# Strobe.net
KiCad netlist of a schematic drawn in EAGLE
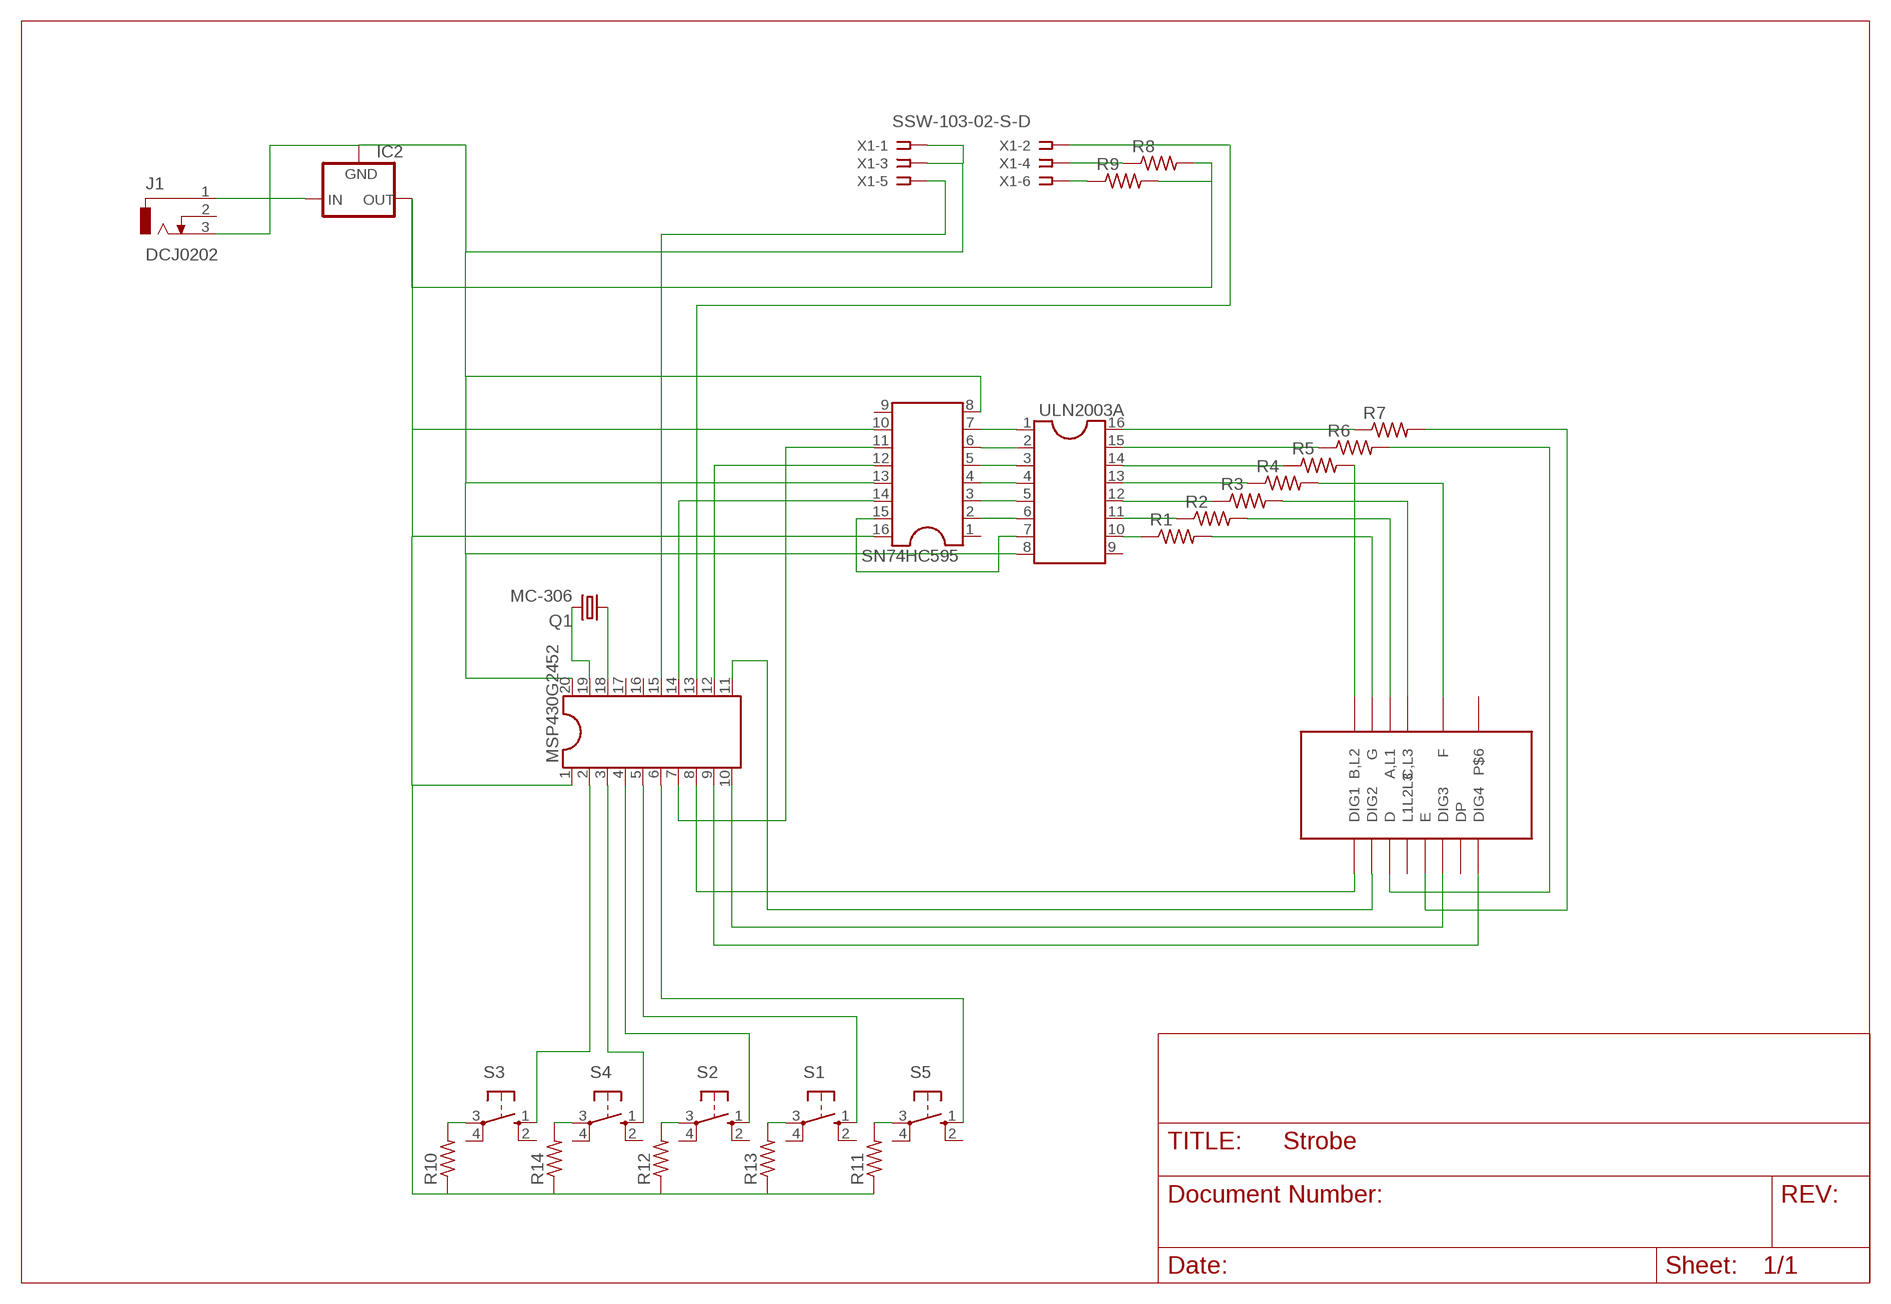
[diagram p0: schematic, sheet 1]

(export (version "E")
  (design (tool "Eeschema 10.0.6"))
  (components
    (comp (ref "IC2")
      (value "78XXS")
      (footprint "eagle-import:78XXS")
      (libsource (lib "eagle-import") (part "78XXS"))
    )
    (comp (ref "J1")
      (value "DCJ0202")
      (footprint "eagle-import:DCJ0202")
      (libsource (lib "eagle-import") (part "DCJ0202"))
    )
    (comp (ref "LTC-4627JS")
      (value "SEG4X7")
      (footprint "eagle-import:HDSP-R")
      (libsource (lib "eagle-import") (part "SEG4X7"))
    )
    (comp (ref "MSP430G2452")
      (value "DIL20S")
      (footprint "eagle-import:SOCKET-20")
      (libsource (lib "eagle-import") (part "DIL20S"))
    )
    (comp (ref "Q1")
      (value "MC-306")
      (footprint "eagle-import:MC-306")
      (fields (field (name "MPN") "MC-306 60.0KHZ  100PPM ,12.5PF"))
      (libsource (lib "eagle-import") (part "MC-306"))
    )
    (comp (ref "R1")
      (value "R-US_0207/7")
      (footprint "eagle-import:0207_7")
      (libsource (lib "eagle-import") (part "R-US_0207/7"))
    )
    (comp (ref "R2")
      (value "R-US_0207/7")
      (footprint "eagle-import:0207_7")
      (libsource (lib "eagle-import") (part "R-US_0207/7"))
    )
    (comp (ref "R3")
      (value "R-US_0207/7")
      (footprint "eagle-import:0207_7")
      (libsource (lib "eagle-import") (part "R-US_0207/7"))
    )
    (comp (ref "R4")
      (value "R-US_0207/7")
      (footprint "eagle-import:0207_7")
      (libsource (lib "eagle-import") (part "R-US_0207/7"))
    )
    (comp (ref "R5")
      (value "R-US_0207/7")
      (footprint "eagle-import:0207_7")
      (libsource (lib "eagle-import") (part "R-US_0207/7"))
    )
    (comp (ref "R6")
      (value "R-US_0207/7")
      (footprint "eagle-import:0207_7")
      (libsource (lib "eagle-import") (part "R-US_0207/7"))
    )
    (comp (ref "R7")
      (value "R-US_0207/7")
      (footprint "eagle-import:0207_7")
      (libsource (lib "eagle-import") (part "R-US_0207/7"))
    )
    (comp (ref "R8")
      (value "R-US_0207/7")
      (footprint "eagle-import:0207_7")
      (libsource (lib "eagle-import") (part "R-US_0207/7"))
    )
    (comp (ref "R9")
      (value "R-US_0207/7")
      (footprint "eagle-import:0207_7")
      (libsource (lib "eagle-import") (part "R-US_0207/7"))
    )
    (comp (ref "R10")
      (value "R-US_0207/7")
      (footprint "eagle-import:0207_7")
      (libsource (lib "eagle-import") (part "R-US_0207/7"))
    )
    (comp (ref "R11")
      (value "R-US_0207/7")
      (footprint "eagle-import:0207_7")
      (libsource (lib "eagle-import") (part "R-US_0207/7"))
    )
    (comp (ref "R12")
      (value "R-US_0207/7")
      (footprint "eagle-import:0207_7")
      (libsource (lib "eagle-import") (part "R-US_0207/7"))
    )
    (comp (ref "R13")
      (value "R-US_0207/7")
      (footprint "eagle-import:0207_7")
      (libsource (lib "eagle-import") (part "R-US_0207/7"))
    )
    (comp (ref "R14")
      (value "R-US_0207/7")
      (footprint "eagle-import:0207_7")
      (libsource (lib "eagle-import") (part "R-US_0207/7"))
    )
    (comp (ref "S1")
      (value "10-XX")
      (footprint "eagle-import:B3F-10XX")
      (fields (field (name "MPN") "B3F-1000"))
      (libsource (lib "eagle-import") (part "10-XX"))
    )
    (comp (ref "S2")
      (value "10-XX")
      (footprint "eagle-import:B3F-10XX")
      (fields (field (name "MPN") "B3F-1000"))
      (libsource (lib "eagle-import") (part "10-XX"))
    )
    (comp (ref "S3")
      (value "10-XX")
      (footprint "eagle-import:B3F-10XX")
      (fields (field (name "MPN") "B3F-1000"))
      (libsource (lib "eagle-import") (part "10-XX"))
    )
    (comp (ref "S4")
      (value "10-XX")
      (footprint "eagle-import:B3F-10XX")
      (fields (field (name "MPN") "B3F-1000"))
      (libsource (lib "eagle-import") (part "10-XX"))
    )
    (comp (ref "S5")
      (value "10-XX")
      (footprint "eagle-import:B3F-10XX")
      (fields (field (name "MPN") "B3F-1000"))
      (libsource (lib "eagle-import") (part "10-XX"))
    )
    (comp (ref "SN74HC595")
      (value "DIL16")
      (footprint "eagle-import:DIL16")
      (libsource (lib "eagle-import") (part "DIL16"))
    )
    (comp (ref "ULN2003A")
      (value "DIL16")
      (footprint "eagle-import:DIL16")
      (libsource (lib "eagle-import") (part "DIL16"))
    )
    (comp (ref "X1")
      (value "SSW-103-02-S-D")
      (footprint "eagle-import:SSW-103-02-S-D")
      (libsource (lib "eagle-import") (part "SSW-103-02-S-D"))
    )
  )
  (nets
    (net (code "1") (name "Net-(IC2-PadIN)") (class "Default")
      (node (ref "IC2") (pin "IN") (pinfunction "IN_IN") (pintype "input"))
      (node (ref "J1") (pin "1") (pinfunction "1_1") (pintype "passive"))
    )
    (net (code "2") (name "Net-(IC2-PadOUT)") (class "Default")
      (node (ref "IC2") (pin "OUT") (pinfunction "OUT_OUT") (pintype "passive"))
      (node (ref "MSP430G2452") (pin "1") (pinfunction "1_1") (pintype "passive"))
      (node (ref "R10") (pin "1") (pinfunction "1_1") (pintype "passive"))
      (node (ref "R11") (pin "1") (pinfunction "1_1") (pintype "passive"))
      (node (ref "R12") (pin "1") (pinfunction "1_1") (pintype "passive"))
      (node (ref "R13") (pin "1") (pinfunction "1_1") (pintype "passive"))
      (node (ref "R14") (pin "1") (pinfunction "1_1") (pintype "passive"))
      (node (ref "R8") (pin "2") (pinfunction "2_2") (pintype "passive"))
      (node (ref "R9") (pin "2") (pinfunction "2_2") (pintype "passive"))
      (node (ref "SN74HC595") (pin "10") (pinfunction "10_10") (pintype "passive"))
      (node (ref "SN74HC595") (pin "16") (pinfunction "16_16") (pintype "passive"))
    )
    (net (code "3") (name "Net-(LTC-4627JS-PadA,L1)") (class "Default")
      (node (ref "LTC-4627JS") (pin "A,L1") (pinfunction "A,L1_A,L1") (pintype "bidirectional"))
      (node (ref "R2") (pin "2") (pinfunction "2_2") (pintype "passive"))
    )
    (net (code "4") (name "Net-(LTC-4627JS-PadB,L2)") (class "Default")
      (node (ref "LTC-4627JS") (pin "B,L2") (pinfunction "B,L2_B,L2") (pintype "bidirectional"))
      (node (ref "R5") (pin "2") (pinfunction "2_2") (pintype "passive"))
    )
    (net (code "5") (name "Net-(LTC-4627JS-PadC,L3)") (class "Default")
      (node (ref "LTC-4627JS") (pin "C,L3") (pinfunction "C,L3_C,L3") (pintype "bidirectional"))
      (node (ref "R3") (pin "2") (pinfunction "2_2") (pintype "passive"))
    )
    (net (code "6") (name "Net-(LTC-4627JS-PadD)") (class "Default")
      (node (ref "LTC-4627JS") (pin "D") (pinfunction "D_D") (pintype "bidirectional"))
      (node (ref "R6") (pin "2") (pinfunction "2_2") (pintype "passive"))
    )
    (net (code "7") (name "Net-(LTC-4627JS-PadDIG1)") (class "Default")
      (node (ref "LTC-4627JS") (pin "DIG1") (pinfunction "DIG1_DIG1") (pintype "bidirectional"))
      (node (ref "MSP430G2452") (pin "8") (pinfunction "8_8") (pintype "passive"))
    )
    (net (code "8") (name "Net-(LTC-4627JS-PadDIG2)") (class "Default")
      (node (ref "LTC-4627JS") (pin "DIG2") (pinfunction "DIG2_DIG2") (pintype "bidirectional"))
      (node (ref "MSP430G2452") (pin "11") (pinfunction "11_11") (pintype "passive"))
    )
    (net (code "9") (name "Net-(LTC-4627JS-PadDIG3)") (class "Default")
      (node (ref "LTC-4627JS") (pin "DIG3") (pinfunction "DIG3_DIG3") (pintype "bidirectional"))
      (node (ref "MSP430G2452") (pin "10") (pinfunction "10_10") (pintype "passive"))
    )
    (net (code "10") (name "Net-(LTC-4627JS-PadDIG4)") (class "Default")
      (node (ref "LTC-4627JS") (pin "DIG4") (pinfunction "DIG4_DIG4") (pintype "bidirectional"))
      (node (ref "MSP430G2452") (pin "9") (pinfunction "9_9") (pintype "passive"))
    )
    (net (code "11") (name "Net-(LTC-4627JS-PadE)") (class "Default")
      (node (ref "LTC-4627JS") (pin "E") (pinfunction "E_E") (pintype "bidirectional"))
      (node (ref "R7") (pin "2") (pinfunction "2_2") (pintype "passive"))
    )
    (net (code "12") (name "Net-(LTC-4627JS-PadF)") (class "Default")
      (node (ref "LTC-4627JS") (pin "F") (pinfunction "F_F") (pintype "bidirectional"))
      (node (ref "R4") (pin "2") (pinfunction "2_2") (pintype "passive"))
    )
    (net (code "13") (name "Net-(LTC-4627JS-PadG)") (class "Default")
      (node (ref "LTC-4627JS") (pin "G") (pinfunction "G_G") (pintype "bidirectional"))
      (node (ref "R1") (pin "2") (pinfunction "2_2") (pintype "passive"))
    )
    (net (code "14") (name "Net-(MSP430G2452-Pad7)") (class "Default")
      (node (ref "MSP430G2452") (pin "7") (pinfunction "7_7") (pintype "passive"))
      (node (ref "SN74HC595") (pin "11") (pinfunction "11_11") (pintype "passive"))
    )
    (net (code "15") (name "Net-(MSP430G2452-Pad12)") (class "Default")
      (node (ref "MSP430G2452") (pin "12") (pinfunction "12_12") (pintype "passive"))
      (node (ref "SN74HC595") (pin "12") (pinfunction "12_12") (pintype "passive"))
    )
    (net (code "16") (name "Net-(MSP430G2452-Pad14)") (class "Default")
      (node (ref "MSP430G2452") (pin "14") (pinfunction "14_14") (pintype "passive"))
      (node (ref "SN74HC595") (pin "14") (pinfunction "14_14") (pintype "passive"))
    )
    (net (code "17") (name "Net-(MSP430G2452-Pad18)") (class "Default")
      (node (ref "MSP430G2452") (pin "18") (pinfunction "18_18") (pintype "passive"))
      (node (ref "Q1") (pin "1") (pinfunction "1_1") (pintype "passive"))
    )
    (net (code "18") (name "Net-(Q1-2)") (class "Default")
      (node (ref "MSP430G2452") (pin "19") (pinfunction "19_19") (pintype "passive"))
      (node (ref "Q1") (pin "4") (pinfunction "2_4") (pintype "passive"))
    )
    (net (code "19") (name "Net-(R1-Pad1)") (class "Default")
      (node (ref "R1") (pin "1") (pinfunction "1_1") (pintype "passive"))
      (node (ref "ULN2003A") (pin "10") (pinfunction "10_10") (pintype "passive"))
    )
    (net (code "20") (name "Net-(R2-Pad1)") (class "Default")
      (node (ref "R2") (pin "1") (pinfunction "1_1") (pintype "passive"))
      (node (ref "ULN2003A") (pin "11") (pinfunction "11_11") (pintype "passive"))
    )
    (net (code "21") (name "Net-(R3-Pad1)") (class "Default")
      (node (ref "R3") (pin "1") (pinfunction "1_1") (pintype "passive"))
      (node (ref "ULN2003A") (pin "12") (pinfunction "12_12") (pintype "passive"))
    )
    (net (code "22") (name "Net-(R4-Pad1)") (class "Default")
      (node (ref "R4") (pin "1") (pinfunction "1_1") (pintype "passive"))
      (node (ref "ULN2003A") (pin "13") (pinfunction "13_13") (pintype "passive"))
    )
    (net (code "23") (name "Net-(R5-Pad1)") (class "Default")
      (node (ref "R5") (pin "1") (pinfunction "1_1") (pintype "passive"))
      (node (ref "ULN2003A") (pin "14") (pinfunction "14_14") (pintype "passive"))
    )
    (net (code "24") (name "Net-(R6-Pad1)") (class "Default")
      (node (ref "R6") (pin "1") (pinfunction "1_1") (pintype "passive"))
      (node (ref "ULN2003A") (pin "15") (pinfunction "15_15") (pintype "passive"))
    )
    (net (code "25") (name "Net-(R7-Pad1)") (class "Default")
      (node (ref "R7") (pin "1") (pinfunction "1_1") (pintype "passive"))
      (node (ref "ULN2003A") (pin "16") (pinfunction "16_16") (pintype "passive"))
    )
    (net (code "26") (name "Net-(S1-P)") (class "Default")
      (node (ref "R13") (pin "2") (pinfunction "2_2") (pintype "passive"))
      (node (ref "S1") (pin "3") (pinfunction "P_3") (pintype "passive"))
    )
    (net (code "27") (name "Net-(S1-S)") (class "Default")
      (node (ref "MSP430G2452") (pin "5") (pinfunction "5_5") (pintype "passive"))
      (node (ref "S1") (pin "1") (pinfunction "S_1") (pintype "passive"))
    )
    (net (code "28") (name "Net-(S2-P)") (class "Default")
      (node (ref "R12") (pin "2") (pinfunction "2_2") (pintype "passive"))
      (node (ref "S2") (pin "3") (pinfunction "P_3") (pintype "passive"))
    )
    (net (code "29") (name "Net-(S2-S)") (class "Default")
      (node (ref "MSP430G2452") (pin "4") (pinfunction "4_4") (pintype "passive"))
      (node (ref "S2") (pin "1") (pinfunction "S_1") (pintype "passive"))
    )
    (net (code "30") (name "Net-(S3-P)") (class "Default")
      (node (ref "R10") (pin "2") (pinfunction "2_2") (pintype "passive"))
      (node (ref "S3") (pin "3") (pinfunction "P_3") (pintype "passive"))
    )
    (net (code "31") (name "Net-(S3-S)") (class "Default")
      (node (ref "MSP430G2452") (pin "2") (pinfunction "2_2") (pintype "passive"))
      (node (ref "S3") (pin "1") (pinfunction "S_1") (pintype "passive"))
    )
    (net (code "32") (name "Net-(S4-P)") (class "Default")
      (node (ref "R14") (pin "2") (pinfunction "2_2") (pintype "passive"))
      (node (ref "S4") (pin "3") (pinfunction "P_3") (pintype "passive"))
    )
    (net (code "33") (name "Net-(S4-S)") (class "Default")
      (node (ref "MSP430G2452") (pin "3") (pinfunction "3_3") (pintype "passive"))
      (node (ref "S4") (pin "1") (pinfunction "S_1") (pintype "passive"))
    )
    (net (code "34") (name "Net-(S5-P)") (class "Default")
      (node (ref "R11") (pin "2") (pinfunction "2_2") (pintype "passive"))
      (node (ref "S5") (pin "3") (pinfunction "P_3") (pintype "passive"))
    )
    (net (code "35") (name "Net-(S5-S)") (class "Default")
      (node (ref "MSP430G2452") (pin "6") (pinfunction "6_6") (pintype "passive"))
      (node (ref "S5") (pin "1") (pinfunction "S_1") (pintype "passive"))
    )
    (net (code "36") (name "Net-(SN74HC595-Pad2)") (class "Default")
      (node (ref "SN74HC595") (pin "2") (pinfunction "2_2") (pintype "passive"))
      (node (ref "ULN2003A") (pin "6") (pinfunction "6_6") (pintype "passive"))
    )
    (net (code "37") (name "Net-(SN74HC595-Pad3)") (class "Default")
      (node (ref "SN74HC595") (pin "3") (pinfunction "3_3") (pintype "passive"))
      (node (ref "ULN2003A") (pin "5") (pinfunction "5_5") (pintype "passive"))
    )
    (net (code "38") (name "Net-(SN74HC595-Pad4)") (class "Default")
      (node (ref "SN74HC595") (pin "4") (pinfunction "4_4") (pintype "passive"))
      (node (ref "ULN2003A") (pin "4") (pinfunction "4_4") (pintype "passive"))
    )
    (net (code "39") (name "Net-(SN74HC595-Pad5)") (class "Default")
      (node (ref "SN74HC595") (pin "5") (pinfunction "5_5") (pintype "passive"))
      (node (ref "ULN2003A") (pin "3") (pinfunction "3_3") (pintype "passive"))
    )
    (net (code "40") (name "Net-(SN74HC595-Pad6)") (class "Default")
      (node (ref "SN74HC595") (pin "6") (pinfunction "6_6") (pintype "passive"))
      (node (ref "ULN2003A") (pin "2") (pinfunction "2_2") (pintype "passive"))
    )
    (net (code "41") (name "Net-(SN74HC595-Pad7)") (class "Default")
      (node (ref "SN74HC595") (pin "7") (pinfunction "7_7") (pintype "passive"))
      (node (ref "ULN2003A") (pin "1") (pinfunction "1_1") (pintype "passive"))
    )
    (net (code "42") (name "Net-(SN74HC595-Pad15)") (class "Default")
      (node (ref "SN74HC595") (pin "15") (pinfunction "15_15") (pintype "passive"))
      (node (ref "ULN2003A") (pin "7") (pinfunction "7_7") (pintype "passive"))
    )
    (net (code "43") (name "Net-(X1B-1)") (class "Default")
      (node (ref "MSP430G2452") (pin "13") (pinfunction "13_13") (pintype "passive"))
      (node (ref "X1") (pin "2") (pinfunction "1_2") (pintype "passive"))
    )
    (net (code "44") (name "Net-(X1C-1)") (class "Default")
      (node (ref "IC2") (pin "GND") (pinfunction "GND_GND") (pintype "input"))
      (node (ref "J1") (pin "3") (pinfunction "3_3") (pintype "passive"))
      (node (ref "MSP430G2452") (pin "20") (pinfunction "20_20") (pintype "passive"))
      (node (ref "SN74HC595") (pin "13") (pinfunction "13_13") (pintype "passive"))
      (node (ref "SN74HC595") (pin "8") (pinfunction "8_8") (pintype "passive"))
      (node (ref "ULN2003A") (pin "8") (pinfunction "8_8") (pintype "passive"))
      (node (ref "X1") (pin "1") (pinfunction "1_1") (pintype "passive"))
      (node (ref "X1") (pin "3") (pinfunction "1_3") (pintype "passive"))
    )
    (net (code "45") (name "Net-(X1D-1)") (class "Default")
      (node (ref "R8") (pin "1") (pinfunction "1_1") (pintype "passive"))
      (node (ref "X1") (pin "4") (pinfunction "1_4") (pintype "passive"))
    )
    (net (code "46") (name "Net-(X1E-1)") (class "Default")
      (node (ref "MSP430G2452") (pin "15") (pinfunction "15_15") (pintype "passive"))
      (node (ref "X1") (pin "5") (pinfunction "1_5") (pintype "passive"))
    )
    (net (code "47") (name "Net-(X1F-1)") (class "Default")
      (node (ref "R9") (pin "1") (pinfunction "1_1") (pintype "passive"))
      (node (ref "X1") (pin "6") (pinfunction "1_6") (pintype "passive"))
    )
    (net (code "48") (name "unconnected-(J1-Pad2)") (class "Default")
      (node (ref "J1") (pin "2") (pinfunction "2_2") (pintype "passive"))
    )
    (net (code "49") (name "unconnected-(LTC-4627JS-L1L2L3-PadL1,L2,L3)") (class "Default")
      (node (ref "LTC-4627JS") (pin "L1,L2,L3") (pinfunction "L1L2L3_L1,L2,L3") (pintype "bidirectional"))
    )
    (net (code "50") (name "unconnected-(LTC-4627JS-P$6-PadNULL)") (class "Default")
      (node (ref "LTC-4627JS") (pin "NULL") (pinfunction "P$6_NULL") (pintype "bidirectional"))
    )
    (net (code "51") (name "unconnected-(LTC-4627JS-PadDP)") (class "Default")
      (node (ref "LTC-4627JS") (pin "DP") (pinfunction "DP_DP") (pintype "bidirectional"))
    )
    (net (code "52") (name "unconnected-(MSP430G2452-Pad16)") (class "Default")
      (node (ref "MSP430G2452") (pin "16") (pinfunction "16_16") (pintype "passive"))
    )
    (net (code "53") (name "unconnected-(MSP430G2452-Pad17)") (class "Default")
      (node (ref "MSP430G2452") (pin "17") (pinfunction "17_17") (pintype "passive"))
    )
    (net (code "54") (name "unconnected-(S1-P1-Pad4)") (class "Default")
      (node (ref "S1") (pin "4") (pinfunction "P1_4") (pintype "passive"))
    )
    (net (code "55") (name "unconnected-(S1-S1-Pad2)") (class "Default")
      (node (ref "S1") (pin "2") (pinfunction "S1_2") (pintype "passive"))
    )
    (net (code "56") (name "unconnected-(S2-P1-Pad4)") (class "Default")
      (node (ref "S2") (pin "4") (pinfunction "P1_4") (pintype "passive"))
    )
    (net (code "57") (name "unconnected-(S2-S1-Pad2)") (class "Default")
      (node (ref "S2") (pin "2") (pinfunction "S1_2") (pintype "passive"))
    )
    (net (code "58") (name "unconnected-(S3-P1-Pad4)") (class "Default")
      (node (ref "S3") (pin "4") (pinfunction "P1_4") (pintype "passive"))
    )
    (net (code "59") (name "unconnected-(S3-S1-Pad2)") (class "Default")
      (node (ref "S3") (pin "2") (pinfunction "S1_2") (pintype "passive"))
    )
    (net (code "60") (name "unconnected-(S4-P1-Pad4)") (class "Default")
      (node (ref "S4") (pin "4") (pinfunction "P1_4") (pintype "passive"))
    )
    (net (code "61") (name "unconnected-(S4-S1-Pad2)") (class "Default")
      (node (ref "S4") (pin "2") (pinfunction "S1_2") (pintype "passive"))
    )
    (net (code "62") (name "unconnected-(S5-P1-Pad4)") (class "Default")
      (node (ref "S5") (pin "4") (pinfunction "P1_4") (pintype "passive"))
    )
    (net (code "63") (name "unconnected-(S5-S1-Pad2)") (class "Default")
      (node (ref "S5") (pin "2") (pinfunction "S1_2") (pintype "passive"))
    )
    (net (code "64") (name "unconnected-(SN74HC595-Pad1)") (class "Default")
      (node (ref "SN74HC595") (pin "1") (pinfunction "1_1") (pintype "passive"))
    )
    (net (code "65") (name "unconnected-(SN74HC595-Pad9)") (class "Default")
      (node (ref "SN74HC595") (pin "9") (pinfunction "9_9") (pintype "passive"))
    )
    (net (code "66") (name "unconnected-(ULN2003A-Pad9)") (class "Default")
      (node (ref "ULN2003A") (pin "9") (pinfunction "9_9") (pintype "passive"))
    )
  )
)
